# 3AND_2.net
KiCad netlist of a schematic drawn in EAGLE
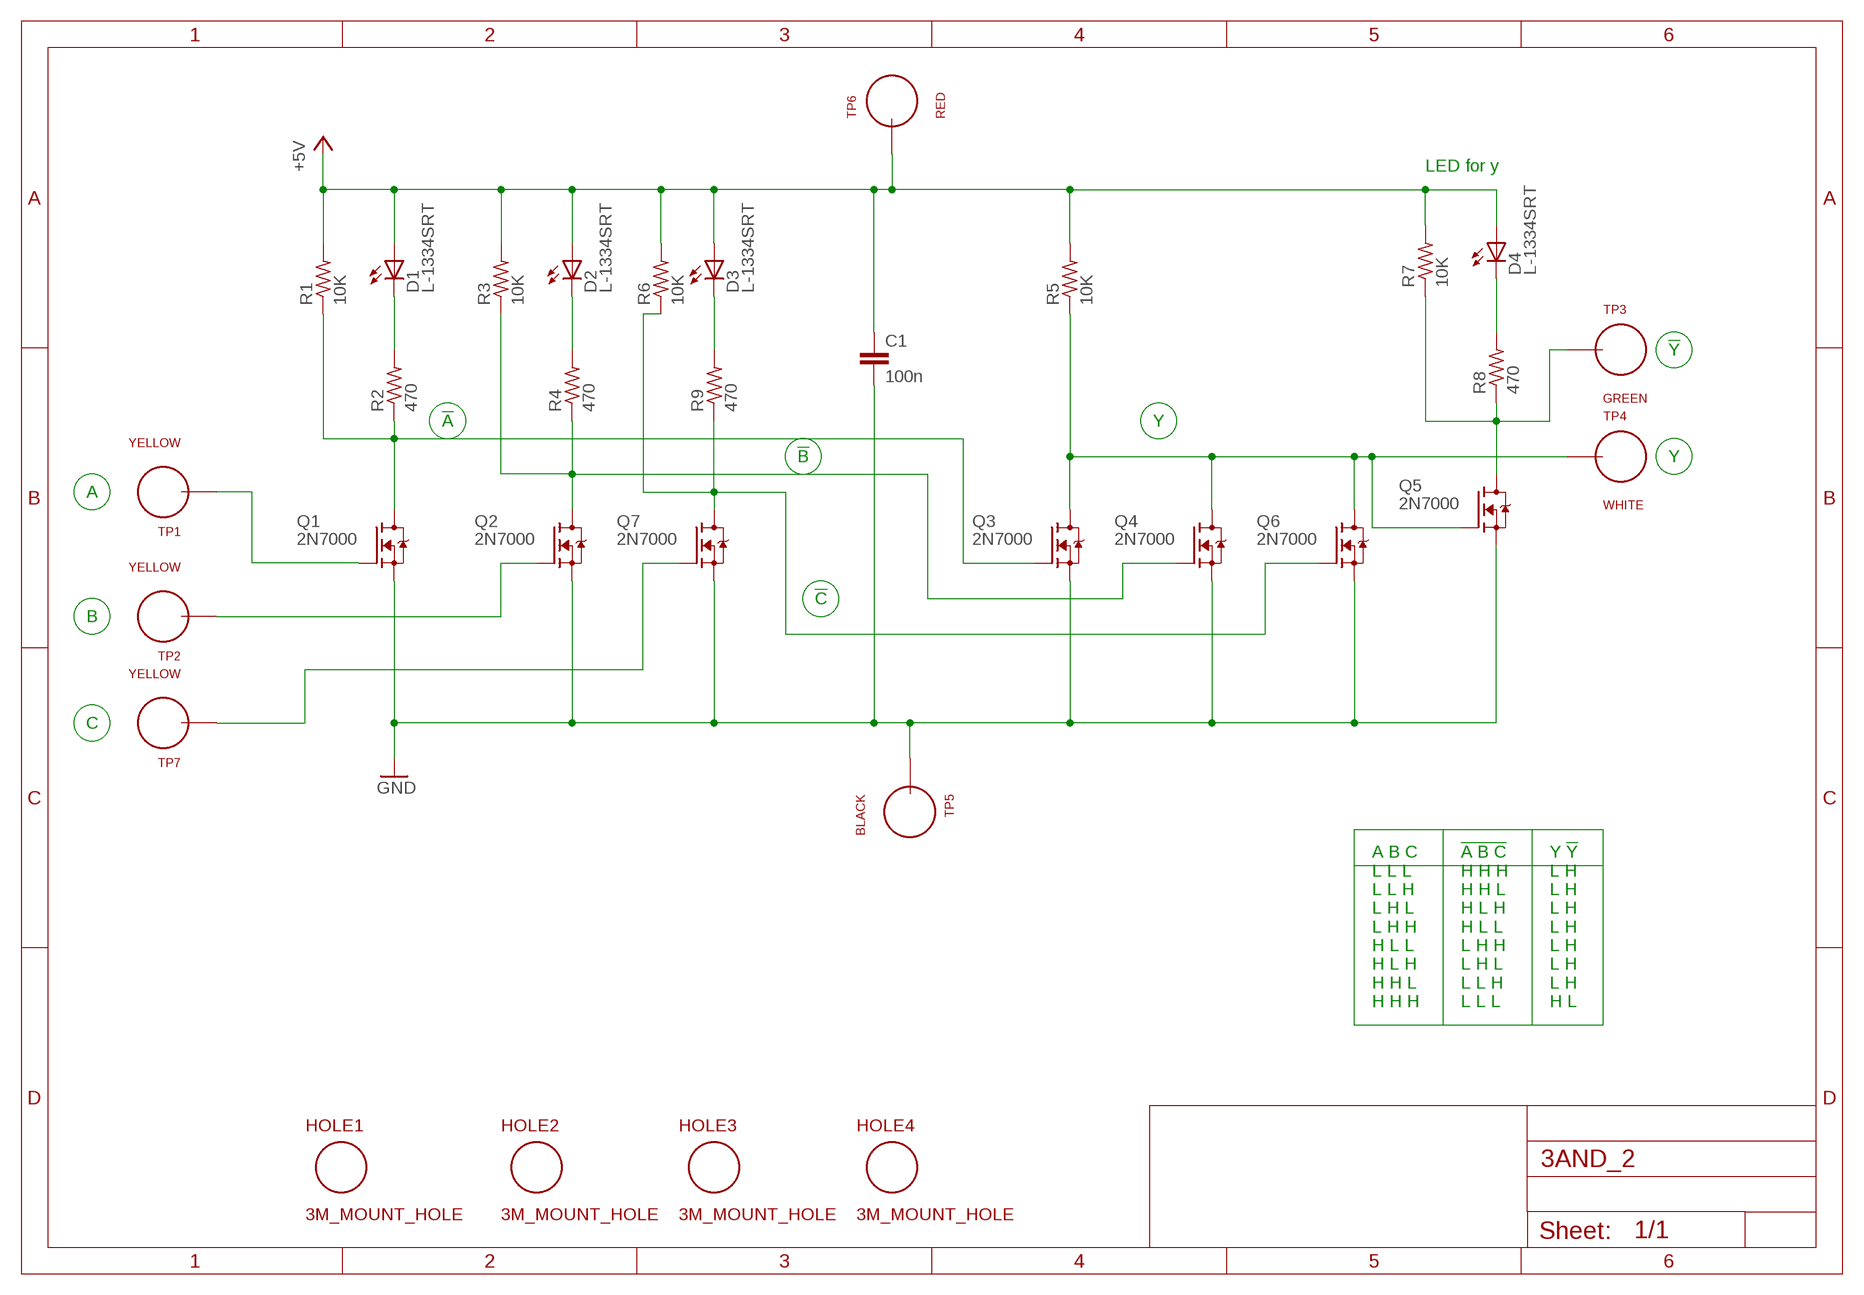
[diagram p0: schematic, sheet 1]

(export (version "E")
  (design (tool "Eeschema 10.0.6"))
  (components
    (comp (ref "C1")
      (value "100n")
      (footprint "eagle-import:CAP_P2INCH")
      (libsource (lib "eagle-import") (part "C_P2INCH"))
    )
    (comp (ref "D1")
      (value "L-1334SRT")
      (footprint "eagle-import:LED3MM")
      (libsource (lib "eagle-import") (part "L-1334SRT"))
    )
    (comp (ref "D2")
      (value "L-1334SRT")
      (footprint "eagle-import:LED3MM")
      (libsource (lib "eagle-import") (part "L-1334SRT"))
    )
    (comp (ref "D3")
      (value "L-1334SRT")
      (footprint "eagle-import:LED3MM")
      (libsource (lib "eagle-import") (part "L-1334SRT"))
    )
    (comp (ref "D4")
      (value "L-1334SRT")
      (footprint "eagle-import:LED3MM")
      (libsource (lib "eagle-import") (part "L-1334SRT"))
    )
    (comp (ref "HOLE1")
      (value "3M_MOUNT_HOLE")
      (footprint "eagle-import:3M_HOLE")
      (libsource (lib "eagle-import") (part "3M_MOUNT_HOLE"))
    )
    (comp (ref "HOLE2")
      (value "3M_MOUNT_HOLE")
      (footprint "eagle-import:3M_HOLE")
      (libsource (lib "eagle-import") (part "3M_MOUNT_HOLE"))
    )
    (comp (ref "HOLE3")
      (value "3M_MOUNT_HOLE")
      (footprint "eagle-import:3M_HOLE")
      (libsource (lib "eagle-import") (part "3M_MOUNT_HOLE"))
    )
    (comp (ref "HOLE4")
      (value "3M_MOUNT_HOLE")
      (footprint "eagle-import:3M_HOLE")
      (libsource (lib "eagle-import") (part "3M_MOUNT_HOLE"))
    )
    (comp (ref "Q1")
      (value "2N7000")
      (footprint "eagle-import:TO92-DGS")
      (libsource (lib "eagle-import") (part "2N7000"))
    )
    (comp (ref "Q2")
      (value "2N7000")
      (footprint "eagle-import:TO92-DGS")
      (libsource (lib "eagle-import") (part "2N7000"))
    )
    (comp (ref "Q3")
      (value "2N7000")
      (footprint "eagle-import:TO92-DGS")
      (libsource (lib "eagle-import") (part "2N7000"))
    )
    (comp (ref "Q4")
      (value "2N7000")
      (footprint "eagle-import:TO92-DGS")
      (libsource (lib "eagle-import") (part "2N7000"))
    )
    (comp (ref "Q5")
      (value "2N7000")
      (footprint "eagle-import:TO92-DGS")
      (libsource (lib "eagle-import") (part "2N7000"))
    )
    (comp (ref "Q6")
      (value "2N7000")
      (footprint "eagle-import:TO92-DGS")
      (libsource (lib "eagle-import") (part "2N7000"))
    )
    (comp (ref "Q7")
      (value "2N7000")
      (footprint "eagle-import:TO92-DGS")
      (libsource (lib "eagle-import") (part "2N7000"))
    )
    (comp (ref "R1")
      (value "10K")
      (footprint "eagle-import:R_P2INCH")
      (libsource (lib "eagle-import") (part "R_P2INCH"))
    )
    (comp (ref "R2")
      (value "470")
      (footprint "eagle-import:R_P2INCH")
      (libsource (lib "eagle-import") (part "R_P2INCH"))
    )
    (comp (ref "R3")
      (value "10K")
      (footprint "eagle-import:R_P2INCH")
      (libsource (lib "eagle-import") (part "R_P2INCH"))
    )
    (comp (ref "R4")
      (value "470")
      (footprint "eagle-import:R_P2INCH")
      (libsource (lib "eagle-import") (part "R_P2INCH"))
    )
    (comp (ref "R5")
      (value "10K")
      (footprint "eagle-import:R_P2INCH")
      (libsource (lib "eagle-import") (part "R_P2INCH"))
    )
    (comp (ref "R6")
      (value "10K")
      (footprint "eagle-import:R_P2INCH")
      (libsource (lib "eagle-import") (part "R_P2INCH"))
    )
    (comp (ref "R7")
      (value "10K")
      (footprint "eagle-import:R_P2INCH")
      (libsource (lib "eagle-import") (part "R_P2INCH"))
    )
    (comp (ref "R8")
      (value "470")
      (footprint "eagle-import:R_P2INCH")
      (libsource (lib "eagle-import") (part "R_P2INCH"))
    )
    (comp (ref "R9")
      (value "470")
      (footprint "eagle-import:R_P2INCH")
      (libsource (lib "eagle-import") (part "R_P2INCH"))
    )
    (comp (ref "TP1")
      (value "YELLOW")
      (footprint "eagle-import:TEST_LOOP")
      (libsource (lib "eagle-import") (part "TEST_LOOP"))
    )
    (comp (ref "TP2")
      (value "YELLOW")
      (footprint "eagle-import:TEST_LOOP")
      (libsource (lib "eagle-import") (part "TEST_LOOP"))
    )
    (comp (ref "TP3")
      (value "GREEN")
      (footprint "eagle-import:TEST_LOOP")
      (libsource (lib "eagle-import") (part "TEST_LOOP"))
    )
    (comp (ref "TP4")
      (value "WHITE")
      (footprint "eagle-import:TEST_LOOP")
      (libsource (lib "eagle-import") (part "TEST_LOOP"))
    )
    (comp (ref "TP5")
      (value "BLACK")
      (footprint "eagle-import:TEST_LOOP")
      (libsource (lib "eagle-import") (part "TEST_LOOP"))
    )
    (comp (ref "TP6")
      (value "RED")
      (footprint "eagle-import:TEST_LOOP")
      (libsource (lib "eagle-import") (part "TEST_LOOP"))
    )
    (comp (ref "TP7")
      (value "YELLOW")
      (footprint "eagle-import:TEST_LOOP")
      (libsource (lib "eagle-import") (part "TEST_LOOP"))
    )
  )
  (nets
    (net (code "1") (name "+5V") (class "Default")
      (node (ref "C1") (pin "1") (pinfunction "1_1") (pintype "passive"))
      (node (ref "D1") (pin "A") (pinfunction "A_A") (pintype "passive"))
      (node (ref "D2") (pin "A") (pinfunction "A_A") (pintype "passive"))
      (node (ref "D3") (pin "A") (pinfunction "A_A") (pintype "passive"))
      (node (ref "D4") (pin "A") (pinfunction "A_A") (pintype "passive"))
      (node (ref "R1") (pin "2") (pinfunction "2_2") (pintype "passive"))
      (node (ref "R3") (pin "2") (pinfunction "2_2") (pintype "passive"))
      (node (ref "R5") (pin "2") (pinfunction "2_2") (pintype "passive"))
      (node (ref "R6") (pin "2") (pinfunction "2_2") (pintype "passive"))
      (node (ref "R7") (pin "2") (pinfunction "2_2") (pintype "passive"))
      (node (ref "TP6") (pin "P$1") (pinfunction "P$1_P$1") (pintype "bidirectional"))
    )
    (net (code "2") (name "GND") (class "Default")
      (node (ref "C1") (pin "2") (pinfunction "2_2") (pintype "passive"))
      (node (ref "Q1") (pin "S") (pinfunction "S_S") (pintype "passive"))
      (node (ref "Q2") (pin "S") (pinfunction "S_S") (pintype "passive"))
      (node (ref "Q3") (pin "S") (pinfunction "S_S") (pintype "passive"))
      (node (ref "Q4") (pin "S") (pinfunction "S_S") (pintype "passive"))
      (node (ref "Q5") (pin "S") (pinfunction "S_S") (pintype "passive"))
      (node (ref "Q6") (pin "S") (pinfunction "S_S") (pintype "passive"))
      (node (ref "Q7") (pin "S") (pinfunction "S_S") (pintype "passive"))
      (node (ref "TP5") (pin "P$1") (pinfunction "P$1_P$1") (pintype "bidirectional"))
    )
    (net (code "3") (name "Net-(D1-C)") (class "Default")
      (node (ref "D1") (pin "K") (pinfunction "C_K") (pintype "passive"))
      (node (ref "R2") (pin "2") (pinfunction "2_2") (pintype "passive"))
    )
    (net (code "4") (name "Net-(D2-C)") (class "Default")
      (node (ref "D2") (pin "K") (pinfunction "C_K") (pintype "passive"))
      (node (ref "R4") (pin "2") (pinfunction "2_2") (pintype "passive"))
    )
    (net (code "5") (name "Net-(D3-C)") (class "Default")
      (node (ref "D3") (pin "K") (pinfunction "C_K") (pintype "passive"))
      (node (ref "R9") (pin "2") (pinfunction "2_2") (pintype "passive"))
    )
    (net (code "6") (name "Net-(D4-C)") (class "Default")
      (node (ref "D4") (pin "K") (pinfunction "C_K") (pintype "passive"))
      (node (ref "R8") (pin "2") (pinfunction "2_2") (pintype "passive"))
    )
    (net (code "7") (name "Net-(Q1-PadD)") (class "Default")
      (node (ref "Q1") (pin "D") (pinfunction "D_D") (pintype "passive"))
      (node (ref "Q3") (pin "G") (pinfunction "G_G") (pintype "passive"))
      (node (ref "R1") (pin "1") (pinfunction "1_1") (pintype "passive"))
      (node (ref "R2") (pin "1") (pinfunction "1_1") (pintype "passive"))
    )
    (net (code "8") (name "Net-(Q1-PadG)") (class "Default")
      (node (ref "Q1") (pin "G") (pinfunction "G_G") (pintype "passive"))
      (node (ref "TP1") (pin "P$1") (pinfunction "P$1_P$1") (pintype "bidirectional"))
    )
    (net (code "9") (name "Net-(Q2-PadD)") (class "Default")
      (node (ref "Q2") (pin "D") (pinfunction "D_D") (pintype "passive"))
      (node (ref "Q4") (pin "G") (pinfunction "G_G") (pintype "passive"))
      (node (ref "R3") (pin "1") (pinfunction "1_1") (pintype "passive"))
      (node (ref "R4") (pin "1") (pinfunction "1_1") (pintype "passive"))
    )
    (net (code "10") (name "Net-(Q2-PadG)") (class "Default")
      (node (ref "Q2") (pin "G") (pinfunction "G_G") (pintype "passive"))
      (node (ref "TP2") (pin "P$1") (pinfunction "P$1_P$1") (pintype "bidirectional"))
    )
    (net (code "11") (name "Net-(Q3-PadD)") (class "Default")
      (node (ref "Q3") (pin "D") (pinfunction "D_D") (pintype "passive"))
      (node (ref "Q4") (pin "D") (pinfunction "D_D") (pintype "passive"))
      (node (ref "Q5") (pin "G") (pinfunction "G_G") (pintype "passive"))
      (node (ref "Q6") (pin "D") (pinfunction "D_D") (pintype "passive"))
      (node (ref "R5") (pin "1") (pinfunction "1_1") (pintype "passive"))
      (node (ref "TP4") (pin "P$1") (pinfunction "P$1_P$1") (pintype "bidirectional"))
    )
    (net (code "12") (name "Net-(Q5-PadD)") (class "Default")
      (node (ref "Q5") (pin "D") (pinfunction "D_D") (pintype "passive"))
      (node (ref "R7") (pin "1") (pinfunction "1_1") (pintype "passive"))
      (node (ref "R8") (pin "1") (pinfunction "1_1") (pintype "passive"))
      (node (ref "TP3") (pin "P$1") (pinfunction "P$1_P$1") (pintype "bidirectional"))
    )
    (net (code "13") (name "Net-(Q6-PadG)") (class "Default")
      (node (ref "Q6") (pin "G") (pinfunction "G_G") (pintype "passive"))
      (node (ref "Q7") (pin "D") (pinfunction "D_D") (pintype "passive"))
      (node (ref "R6") (pin "1") (pinfunction "1_1") (pintype "passive"))
      (node (ref "R9") (pin "1") (pinfunction "1_1") (pintype "passive"))
    )
    (net (code "14") (name "Net-(Q7-PadG)") (class "Default")
      (node (ref "Q7") (pin "G") (pinfunction "G_G") (pintype "passive"))
      (node (ref "TP7") (pin "P$1") (pinfunction "P$1_P$1") (pintype "bidirectional"))
    )
  )
)
